# blink1mk3_micro1.net
KiCad netlist of a schematic drawn in EAGLE
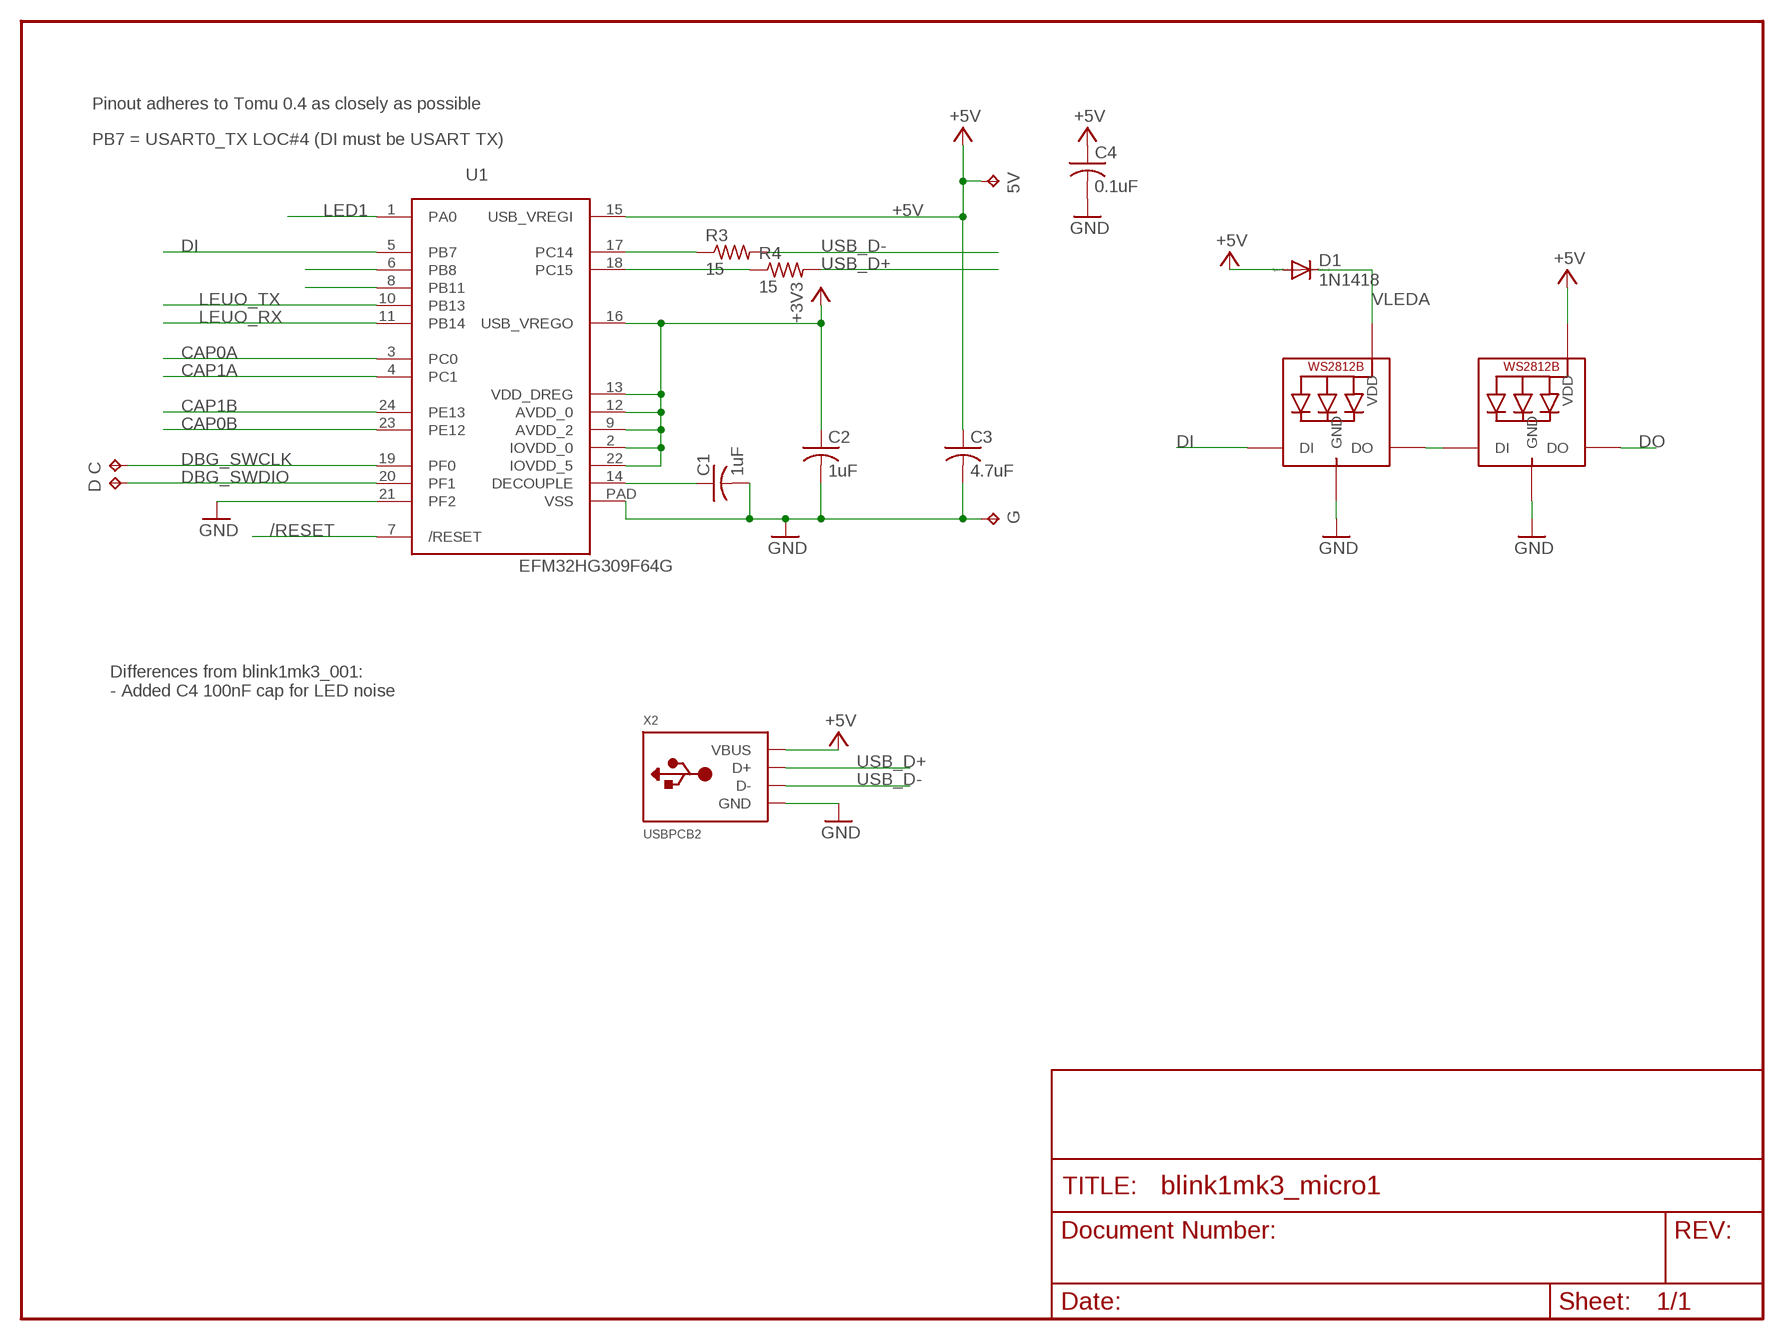
[diagram p0: schematic, sheet 1]

(export (version "E")
  (design (tool "Eeschema 10.0.6"))
  (components
    (comp (ref "5V")
      (value "TPTP10R")
      (footprint "eagle-import:TP10R")
      (libsource (lib "eagle-import") (part "TPTP10R"))
    )
    (comp (ref "C")
      (value "TPTP10R")
      (footprint "eagle-import:TP10R")
      (libsource (lib "eagle-import") (part "TPTP10R"))
    )
    (comp (ref "C1")
      (value "1uF")
      (footprint "eagle-import:C0402")
      (libsource (lib "eagle-import") (part "C-USC0402"))
    )
    (comp (ref "C2")
      (value "1uF")
      (footprint "eagle-import:C0402")
      (libsource (lib "eagle-import") (part "C-USC0402"))
    )
    (comp (ref "C3")
      (value "4.7uF")
      (footprint "eagle-import:C0402")
      (libsource (lib "eagle-import") (part "C-USC0402"))
    )
    (comp (ref "C4")
      (value "0.1uF")
      (footprint "eagle-import:C0402")
      (libsource (lib "eagle-import") (part "C-USC0402"))
    )
    (comp (ref "D")
      (value "TPTP10R")
      (footprint "eagle-import:TP10R")
      (libsource (lib "eagle-import") (part "TPTP10R"))
    )
    (comp (ref "D1")
      (value "1N1418")
      (footprint "eagle-import:SOD523")
      (libsource (lib "eagle-import") (part "DIODE-SOD523"))
    )
    (comp (ref "G")
      (value "TPTP10R")
      (footprint "eagle-import:TP10R")
      (libsource (lib "eagle-import") (part "TPTP10R"))
    )
    (comp (ref "LED1")
      (value "WS2812B4020SIDE")
      (footprint "eagle-import:SK6812-SIDE")
      (libsource (lib "eagle-import") (part "WS2812B4020SIDE"))
    )
    (comp (ref "LED2")
      (value "WS2812B4020SIDE")
      (footprint "eagle-import:SK6812-SIDE")
      (libsource (lib "eagle-import") (part "WS2812B4020SIDE"))
    )
    (comp (ref "R3")
      (value "15")
      (footprint "eagle-import:R0402")
      (libsource (lib "eagle-import") (part "R-US_R0402"))
    )
    (comp (ref "R4")
      (value "15")
      (footprint "eagle-import:R0402")
      (libsource (lib "eagle-import") (part "R-US_R0402"))
    )
    (comp (ref "U1")
      (value "EFM32HG309F64G")
      (footprint "eagle-import:QFN24PAD")
      (libsource (lib "eagle-import") (part "EFM32HG309F64G"))
    )
    (comp (ref "X2")
      (value "USBPCB2")
      (footprint "eagle-import:USB-A-PCB-2")
      (libsource (lib "eagle-import") (part "USBPCB2"))
    )
  )
  (nets
    (net (code "1") (name "+3V3") (class "Default")
      (node (ref "C2") (pin "1") (pinfunction "1_1") (pintype "passive"))
      (node (ref "U1") (pin "12") (pinfunction "AVDD_0_12") (pintype "bidirectional"))
      (node (ref "U1") (pin "13") (pinfunction "VDD_DREG_13") (pintype "bidirectional"))
      (node (ref "U1") (pin "16") (pinfunction "USB_VREGO_16") (pintype "bidirectional"))
      (node (ref "U1") (pin "2") (pinfunction "IOVDD_0_2") (pintype "bidirectional"))
      (node (ref "U1") (pin "22") (pinfunction "IOVDD_5_22") (pintype "bidirectional"))
      (node (ref "U1") (pin "9") (pinfunction "AVDD_2_9") (pintype "bidirectional"))
    )
    (net (code "2") (name "+5V") (class "Default")
      (node (ref "5V") (pin "TP") (pinfunction "TP_TP") (pintype "input"))
      (node (ref "C3") (pin "1") (pinfunction "1_1") (pintype "passive"))
      (node (ref "C4") (pin "1") (pinfunction "1_1") (pintype "passive"))
      (node (ref "D1") (pin "A") (pinfunction "A_A") (pintype "passive"))
      (node (ref "LED2") (pin "1-VDD") (pinfunction "VDD_1-VDD") (pintype "power_in"))
      (node (ref "U1") (pin "15") (pinfunction "USB_VREGI_15") (pintype "bidirectional"))
      (node (ref "X2") (pin "5V") (pinfunction "VBUS_5V") (pintype "power_in"))
    )
    (net (code "3") (name "/CAP0A") (class "Default")
      (node (ref "U1") (pin "3") (pinfunction "PC0_3") (pintype "bidirectional"))
    )
    (net (code "4") (name "/CAP0B") (class "Default")
      (node (ref "U1") (pin "23") (pinfunction "PE12_23") (pintype "bidirectional"))
    )
    (net (code "5") (name "/CAP1A") (class "Default")
      (node (ref "U1") (pin "4") (pinfunction "PC1_4") (pintype "bidirectional"))
    )
    (net (code "6") (name "/CAP1B") (class "Default")
      (node (ref "U1") (pin "24") (pinfunction "PE13_24") (pintype "bidirectional"))
    )
    (net (code "7") (name "/DBG_SWCLK") (class "Default")
      (node (ref "C") (pin "TP") (pinfunction "TP_TP") (pintype "input"))
      (node (ref "U1") (pin "19") (pinfunction "PF0_19") (pintype "bidirectional"))
    )
    (net (code "8") (name "/DBG_SWDIO") (class "Default")
      (node (ref "D") (pin "TP") (pinfunction "TP_TP") (pintype "input"))
      (node (ref "U1") (pin "20") (pinfunction "PF1_20") (pintype "bidirectional"))
    )
    (net (code "9") (name "/DI") (class "Default")
      (node (ref "LED1") (pin "4-DIN") (pinfunction "DI_4-DIN") (pintype "input"))
      (node (ref "U1") (pin "5") (pinfunction "PB7_5") (pintype "bidirectional"))
    )
    (net (code "10") (name "/DO") (class "Default")
      (node (ref "LED2") (pin "2-DOUT") (pinfunction "DO_2-DOUT") (pintype "output"))
    )
    (net (code "11") (name "/LED1") (class "Default")
      (node (ref "U1") (pin "1") (pinfunction "PA0_1") (pintype "bidirectional"))
    )
    (net (code "12") (name "/LEUO_RX") (class "Default")
      (node (ref "U1") (pin "11") (pinfunction "PB14_11") (pintype "bidirectional"))
    )
    (net (code "13") (name "/LEUO_TX") (class "Default")
      (node (ref "U1") (pin "10") (pinfunction "PB13_10") (pintype "bidirectional"))
    )
    (net (code "14") (name "/USB_D+") (class "Default")
      (node (ref "R4") (pin "2") (pinfunction "2_2") (pintype "passive"))
      (node (ref "X2") (pin "USB_P") (pinfunction "D+_USB_P") (pintype "bidirectional"))
    )
    (net (code "15") (name "/USB_D-") (class "Default")
      (node (ref "R3") (pin "2") (pinfunction "2_2") (pintype "passive"))
      (node (ref "X2") (pin "USB_M") (pinfunction "D-_USB_M") (pintype "bidirectional"))
    )
    (net (code "16") (name "/VLEDA") (class "Default")
      (node (ref "D1") (pin "C") (pinfunction "C_C") (pintype "passive"))
      (node (ref "LED1") (pin "1-VDD") (pinfunction "VDD_1-VDD") (pintype "power_in"))
    )
    (net (code "17") (name "/{slash}RESET") (class "Default")
      (node (ref "U1") (pin "7") (pinfunction "/RESET_7") (pintype "bidirectional"))
    )
    (net (code "18") (name "GND") (class "Default")
      (node (ref "C1") (pin "2") (pinfunction "2_2") (pintype "passive"))
      (node (ref "C2") (pin "2") (pinfunction "2_2") (pintype "passive"))
      (node (ref "C3") (pin "2") (pinfunction "2_2") (pintype "passive"))
      (node (ref "C4") (pin "2") (pinfunction "2_2") (pintype "passive"))
      (node (ref "G") (pin "TP") (pinfunction "TP_TP") (pintype "input"))
      (node (ref "LED1") (pin "3-GND") (pinfunction "GND_3-GND") (pintype "power_in"))
      (node (ref "LED2") (pin "3-GND") (pinfunction "GND_3-GND") (pintype "power_in"))
      (node (ref "U1") (pin "21") (pinfunction "PF2_21") (pintype "bidirectional"))
      (node (ref "U1") (pin "PAD") (pinfunction "VSS_PAD") (pintype "bidirectional"))
      (node (ref "X2") (pin "GND") (pinfunction "GND_GND") (pintype "power_in"))
    )
    (net (code "19") (name "Net-(LED1-DO)") (class "Default")
      (node (ref "LED1") (pin "2-DOUT") (pinfunction "DO_2-DOUT") (pintype "output"))
      (node (ref "LED2") (pin "4-DIN") (pinfunction "DI_4-DIN") (pintype "input"))
    )
    (net (code "20") (name "Net-(U1-DECOUPLE)") (class "Default")
      (node (ref "C1") (pin "1") (pinfunction "1_1") (pintype "passive"))
      (node (ref "U1") (pin "14") (pinfunction "DECOUPLE_14") (pintype "bidirectional"))
    )
    (net (code "21") (name "Net-(U1-PC14)") (class "Default")
      (node (ref "R3") (pin "1") (pinfunction "1_1") (pintype "passive"))
      (node (ref "U1") (pin "17") (pinfunction "PC14_17") (pintype "bidirectional"))
    )
    (net (code "22") (name "Net-(U1-PC15)") (class "Default")
      (node (ref "R4") (pin "1") (pinfunction "1_1") (pintype "passive"))
      (node (ref "U1") (pin "18") (pinfunction "PC15_18") (pintype "bidirectional"))
    )
    (net (code "23") (name "unconnected-(U1-PB8-Pad6)") (class "Default")
      (node (ref "U1") (pin "6") (pinfunction "PB8_6") (pintype "bidirectional"))
    )
    (net (code "24") (name "unconnected-(U1-PB11-Pad8)") (class "Default")
      (node (ref "U1") (pin "8") (pinfunction "PB11_8") (pintype "bidirectional"))
    )
  )
)
